# ESP32_Component.net
KiCad netlist of a schematic drawn in Altium Designer
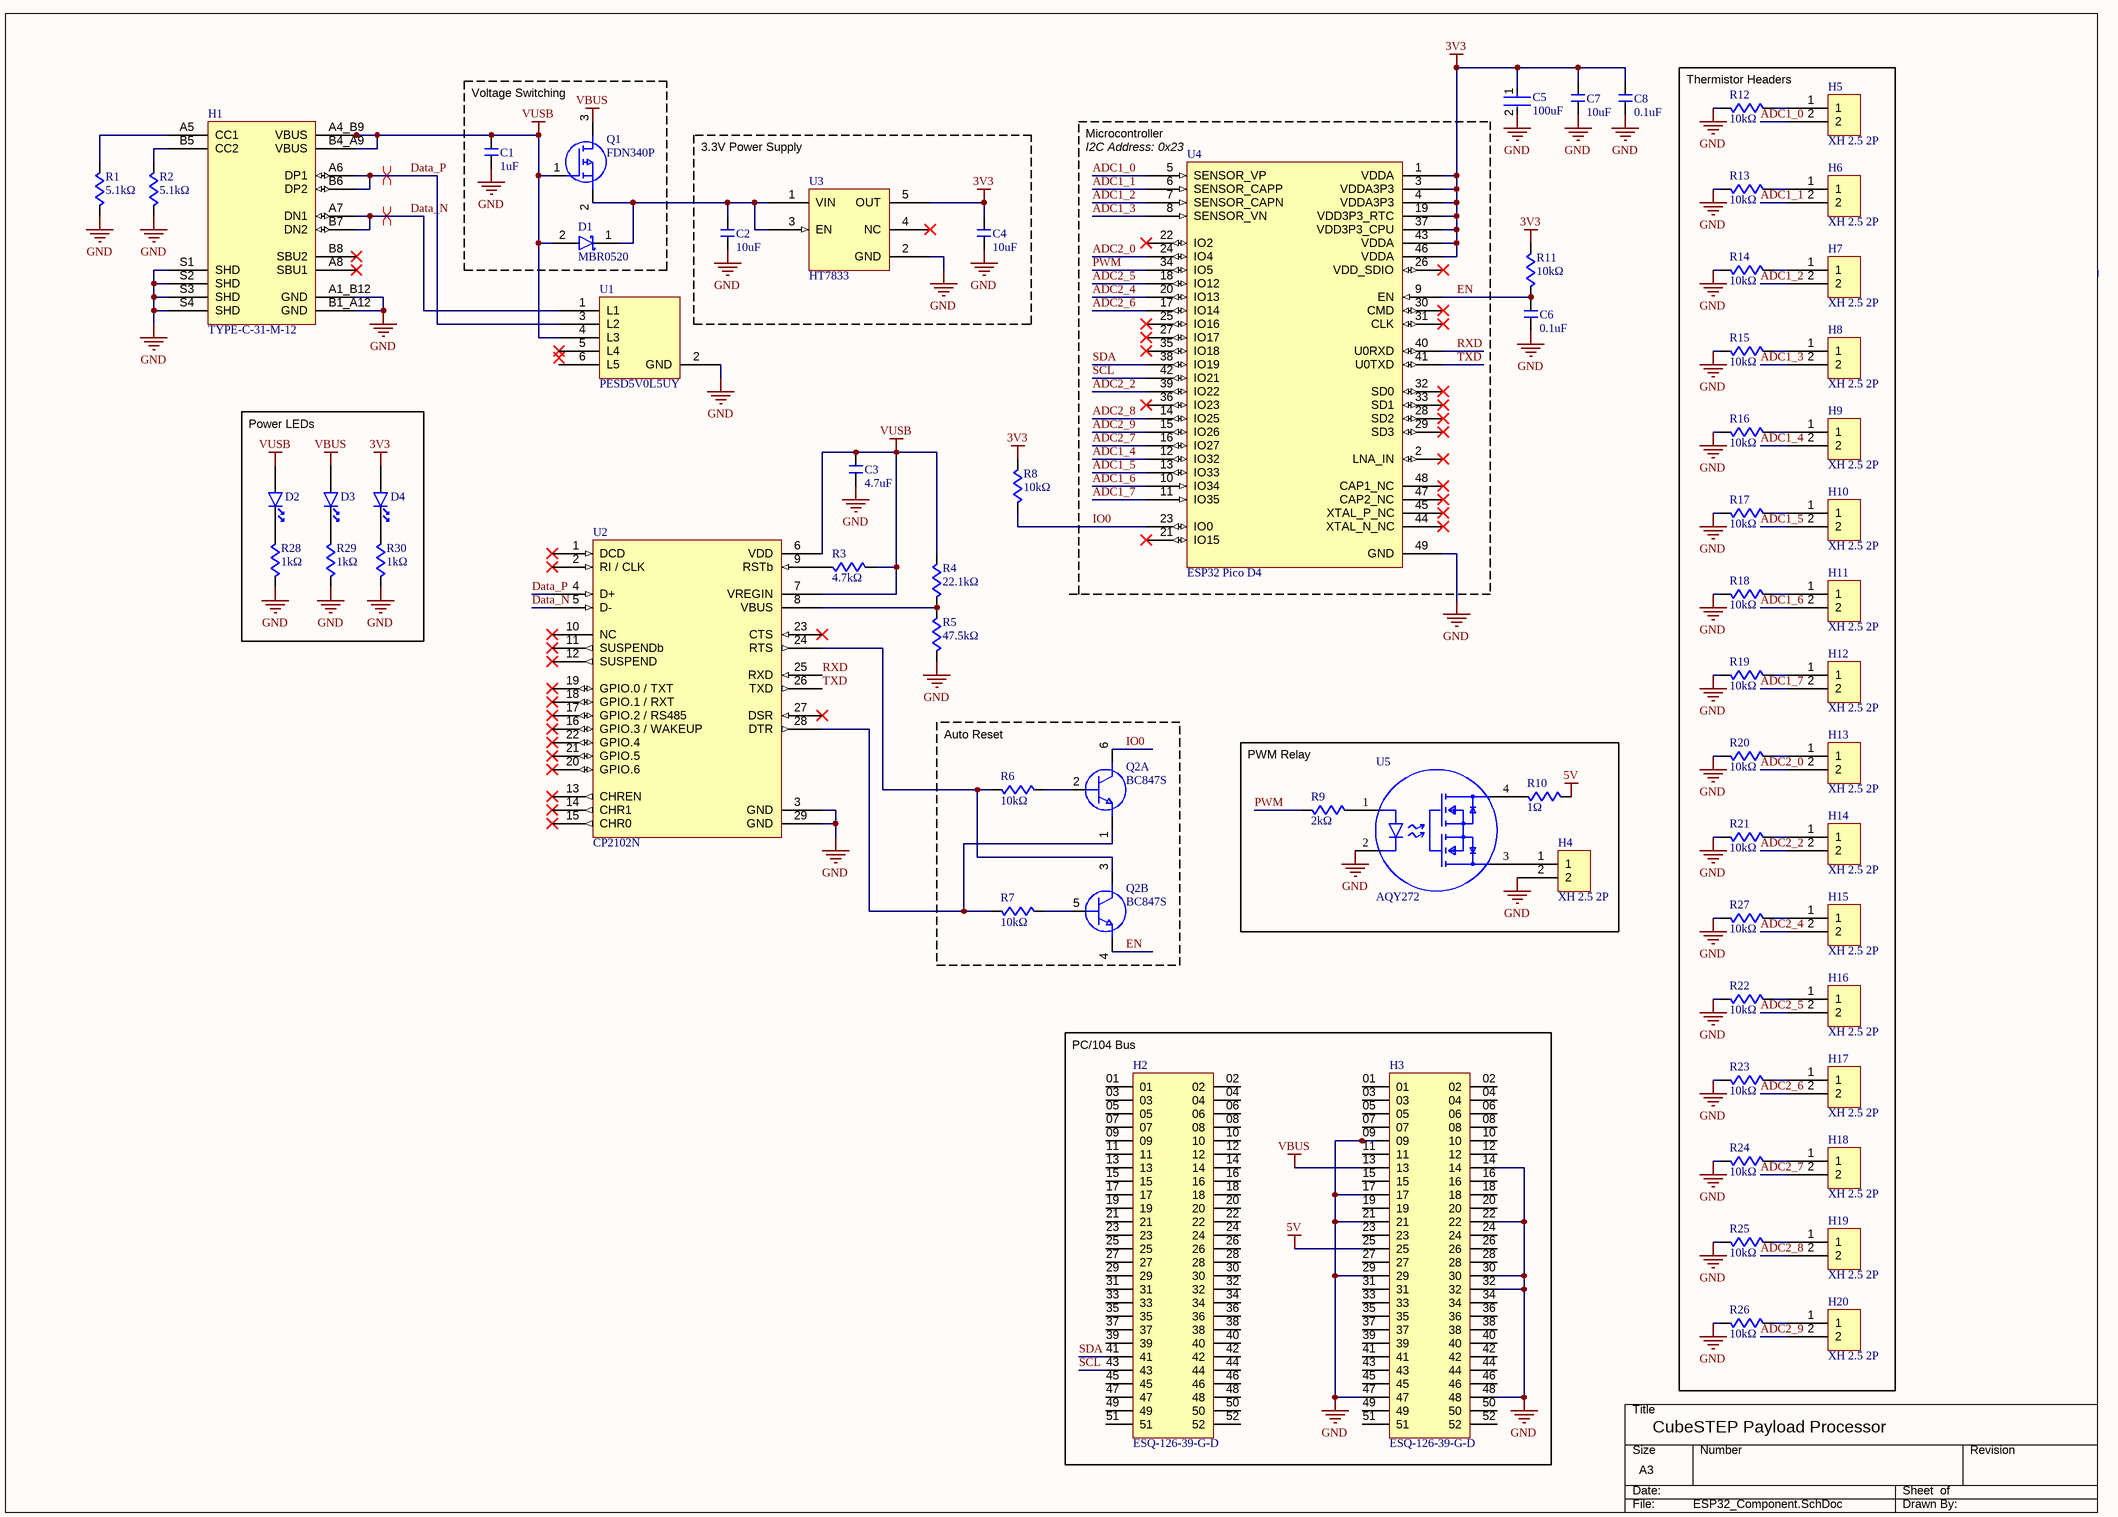
[diagram p0: ESP32_Component.SchDoc]

(export (version "E")
  (design (tool "Eeschema 10.0.6"))
  (components
    (comp (ref "C1")
      (value "1uF")
      (footprint "FP-GRM155-0_05-MFG")
      (description "±10% 16V X5R SMD 0402")
      (fields (field (name "TOLERANCE") "±10%") (field (name "MANUFACTURER") "Murata Electronics"))
      (libsource (lib "CubeSTEP Payload") (part "02cd4be3c70576c341d710602a673aa"))
    )
    (comp (ref "C2")
      (value "10uF")
      (footprint "FP-GRM21B-0_1-MFG")
      (description "±10% 16V B SMD 0805")
      (fields (field (name "PART NUMBER") "GRM21BB31C106KE15L") (field (name "TOLERANCE") "±10%"))
      (libsource (lib "CubeSTEP Payload") (part "b4654b650e69147ec39a6b967a45e02"))
    )
    (comp (ref "C3")
      (value "4.7uF")
      (footprint "TCC0402X5R104M160AT-Footprint-1")
      (description "±20% 16V X5R SMD 0402")
      (fields (field (name "TOLERANCE") "±20%") (field (name "MANUFACTURER") "--"))
      (libsource (lib "CubeSTEP Payload") (part "CM05X5R475M16AH"))
    )
    (comp (ref "C4")
      (value "10uF")
      (footprint "FP-GRM21B-0_1-MFG")
      (description "±10% 16V B SMD 0805")
      (fields (field (name "PART NUMBER") "GRM21BB31C106KE15L") (field (name "TOLERANCE") "±10%"))
      (libsource (lib "CubeSTEP Payload") (part "b4654b650e69147ec39a6b967a45e02"))
    )
    (comp (ref "C5")
      (value "100uF")
      (footprint "CAPC3216X16N")
      (description "±20% 6.3V X5R SMD 1206")
      (fields (field (name "TOLERANCE") "±20%") (field (name "PART NUMBER") "JMK316BJ107ML-T"))
      (libsource (lib "") (part "b4654b650e69147ec39a6b967a45e02_1"))
    )
    (comp (ref "C6")
      (value "0.1uF")
      (footprint "TCC0402X5R104M160AT-Footprint-1")
      (description "±20% 16V X5R SMD 0402")
      (fields (field (name "PART NUMBER") "TCC0402X5R104M160AT") (field (name "MANUFACTURER") "CCTC"))
      (libsource (lib "CubeSTEP Payload") (part "TCC0402X5R104M160AT-Symbol-1"))
    )
    (comp (ref "C7")
      (value "10uF")
      (footprint "FP-GRM21B-0_1-MFG")
      (description "±10% 16V B SMD 0805")
      (fields (field (name "PART NUMBER") "GRM21BB31C106KE15L") (field (name "TOLERANCE") "±10%"))
      (libsource (lib "CubeSTEP Payload") (part "b4654b650e69147ec39a6b967a45e02"))
    )
    (comp (ref "C8")
      (value "0.1uF")
      (footprint "TCC0402X5R104M160AT-Footprint-1")
      (description "±20% 16V X5R SMD 0402")
      (fields (field (name "PART NUMBER") "TCC0402X5R104M160AT") (field (name "MANUFACTURER") "CCTC"))
      (libsource (lib "CubeSTEP Payload") (part "TCC0402X5R104M160AT-Symbol-1"))
    )
    (comp (ref "D1")
      (value "MBR0520")
      (footprint "FP-425-04-MFG")
      (description "Rectifier Diode, Schottky, 1 Phase, 1 Element, 0.5A, 20V V(RRM), Silicon")
      (libsource (lib "CubeSTEP Payload") (part "1d6ec82d83fb6aee721767c19dac4b9"))
    )
    (comp (ref "D2")
      (value "NCD0603R2")
      (footprint "LED0603")
      (libsource (lib "CubeSTEP Payload") (part "8706943c75ba83719d021d2fdc84c58"))
    )
    (comp (ref "D3")
      (value "NCD0603R2")
      (footprint "LED0603")
      (libsource (lib "CubeSTEP Payload") (part "8706943c75ba83719d021d2fdc84c58"))
    )
    (comp (ref "D4")
      (value "NCD0603R2")
      (footprint "LED0603")
      (libsource (lib "CubeSTEP Payload") (part "8706943c75ba83719d021d2fdc84c58"))
    )
    (comp (ref "H1")
      (value "TYPE-C-31-M-12")
      (footprint "TYPE-C-31-M-12-Footprint-1")
      (description "5A 1 16P Female Type-C SMD USB Connectors ROHS")
      (libsource (lib "CubeSTEP Payload") (part "TYPE-C-31-M-12-Symbol-1"))
    )
    (comp (ref "H2")
      (value "ESQ-126-39-G-D")
      (footprint "ESQ-126-39-G-D-Footprint-1")
      (libsource (lib "CubeSTEP Payload") (part "ESQ-126-39-G-D-Symbol-1"))
    )
    (comp (ref "H3")
      (value "ESQ-126-39-G-D")
      (footprint "ESQ-126-39-G-D-Footprint-1")
      (libsource (lib "CubeSTEP Payload") (part "ESQ-126-39-G-D-Symbol-1"))
    )
    (comp (ref "H4")
      (value "XH 2.5 2P")
      (footprint "W-2501R02P-N000-Footprint-1")
      (description "1x2P XH 1 2.5mm 2 Brass Push-Pull,P=2.5mm Wire To Board / Wire To Wire Connector ROHS")
      (fields (field (name "MANUFACTURER") "Ckmtw(Shenzhen Cankemeng)"))
      (libsource (lib "CubeSTEP Payload") (part "W-2501R02P-N000"))
    )
    (comp (ref "H5")
      (value "XH 2.5 2P")
      (footprint "W-2501R02P-N000-Footprint-1")
      (description "1x2P XH 1 2.5mm 2 Brass Push-Pull,P=2.5mm Wire To Board / Wire To Wire Connector ROHS")
      (fields (field (name "MANUFACTURER") "Ckmtw(Shenzhen Cankemeng)"))
      (libsource (lib "CubeSTEP Payload") (part "W-2501R02P-N000"))
    )
    (comp (ref "H6")
      (value "XH 2.5 2P")
      (footprint "W-2501R02P-N000-Footprint-1")
      (description "1x2P XH 1 2.5mm 2 Brass Push-Pull,P=2.5mm Wire To Board / Wire To Wire Connector ROHS")
      (fields (field (name "MANUFACTURER") "Ckmtw(Shenzhen Cankemeng)"))
      (libsource (lib "CubeSTEP Payload") (part "W-2501R02P-N000"))
    )
    (comp (ref "H7")
      (value "XH 2.5 2P")
      (footprint "W-2501R02P-N000-Footprint-1")
      (description "1x2P XH 1 2.5mm 2 Brass Push-Pull,P=2.5mm Wire To Board / Wire To Wire Connector ROHS")
      (fields (field (name "MANUFACTURER") "Ckmtw(Shenzhen Cankemeng)"))
      (libsource (lib "CubeSTEP Payload") (part "W-2501R02P-N000"))
    )
    (comp (ref "H8")
      (value "XH 2.5 2P")
      (footprint "W-2501R02P-N000-Footprint-1")
      (description "1x2P XH 1 2.5mm 2 Brass Push-Pull,P=2.5mm Wire To Board / Wire To Wire Connector ROHS")
      (fields (field (name "MANUFACTURER") "Ckmtw(Shenzhen Cankemeng)"))
      (libsource (lib "CubeSTEP Payload") (part "W-2501R02P-N000"))
    )
    (comp (ref "H9")
      (value "XH 2.5 2P")
      (footprint "W-2501R02P-N000-Footprint-1")
      (description "1x2P XH 1 2.5mm 2 Brass Push-Pull,P=2.5mm Wire To Board / Wire To Wire Connector ROHS")
      (fields (field (name "MANUFACTURER") "Ckmtw(Shenzhen Cankemeng)"))
      (libsource (lib "CubeSTEP Payload") (part "W-2501R02P-N000"))
    )
    (comp (ref "H10")
      (value "XH 2.5 2P")
      (footprint "W-2501R02P-N000-Footprint-1")
      (description "1x2P XH 1 2.5mm 2 Brass Push-Pull,P=2.5mm Wire To Board / Wire To Wire Connector ROHS")
      (fields (field (name "MANUFACTURER") "Ckmtw(Shenzhen Cankemeng)"))
      (libsource (lib "CubeSTEP Payload") (part "W-2501R02P-N000"))
    )
    (comp (ref "H11")
      (value "XH 2.5 2P")
      (footprint "W-2501R02P-N000-Footprint-1")
      (description "1x2P XH 1 2.5mm 2 Brass Push-Pull,P=2.5mm Wire To Board / Wire To Wire Connector ROHS")
      (fields (field (name "MANUFACTURER") "Ckmtw(Shenzhen Cankemeng)"))
      (libsource (lib "CubeSTEP Payload") (part "W-2501R02P-N000"))
    )
    (comp (ref "H12")
      (value "XH 2.5 2P")
      (footprint "W-2501R02P-N000-Footprint-1")
      (description "1x2P XH 1 2.5mm 2 Brass Push-Pull,P=2.5mm Wire To Board / Wire To Wire Connector ROHS")
      (fields (field (name "MANUFACTURER") "Ckmtw(Shenzhen Cankemeng)"))
      (libsource (lib "CubeSTEP Payload") (part "W-2501R02P-N000"))
    )
    (comp (ref "H13")
      (value "XH 2.5 2P")
      (footprint "W-2501R02P-N000-Footprint-1")
      (description "1x2P XH 1 2.5mm 2 Brass Push-Pull,P=2.5mm Wire To Board / Wire To Wire Connector ROHS")
      (fields (field (name "MANUFACTURER") "Ckmtw(Shenzhen Cankemeng)"))
      (libsource (lib "CubeSTEP Payload") (part "W-2501R02P-N000"))
    )
    (comp (ref "H14")
      (value "XH 2.5 2P")
      (footprint "W-2501R02P-N000-Footprint-1")
      (description "1x2P XH 1 2.5mm 2 Brass Push-Pull,P=2.5mm Wire To Board / Wire To Wire Connector ROHS")
      (fields (field (name "MANUFACTURER") "Ckmtw(Shenzhen Cankemeng)"))
      (libsource (lib "CubeSTEP Payload") (part "W-2501R02P-N000"))
    )
    (comp (ref "H15")
      (value "XH 2.5 2P")
      (footprint "W-2501R02P-N000-Footprint-1")
      (description "1x2P XH 1 2.5mm 2 Brass Push-Pull,P=2.5mm Wire To Board / Wire To Wire Connector ROHS")
      (fields (field (name "MANUFACTURER") "Ckmtw(Shenzhen Cankemeng)"))
      (libsource (lib "CubeSTEP Payload") (part "W-2501R02P-N000"))
    )
    (comp (ref "H16")
      (value "XH 2.5 2P")
      (footprint "W-2501R02P-N000-Footprint-1")
      (description "1x2P XH 1 2.5mm 2 Brass Push-Pull,P=2.5mm Wire To Board / Wire To Wire Connector ROHS")
      (fields (field (name "MANUFACTURER") "Ckmtw(Shenzhen Cankemeng)"))
      (libsource (lib "CubeSTEP Payload") (part "W-2501R02P-N000"))
    )
    (comp (ref "H17")
      (value "XH 2.5 2P")
      (footprint "W-2501R02P-N000-Footprint-1")
      (description "1x2P XH 1 2.5mm 2 Brass Push-Pull,P=2.5mm Wire To Board / Wire To Wire Connector ROHS")
      (fields (field (name "MANUFACTURER") "Ckmtw(Shenzhen Cankemeng)"))
      (libsource (lib "CubeSTEP Payload") (part "W-2501R02P-N000"))
    )
    (comp (ref "H18")
      (value "XH 2.5 2P")
      (footprint "W-2501R02P-N000-Footprint-1")
      (description "1x2P XH 1 2.5mm 2 Brass Push-Pull,P=2.5mm Wire To Board / Wire To Wire Connector ROHS")
      (fields (field (name "MANUFACTURER") "Ckmtw(Shenzhen Cankemeng)"))
      (libsource (lib "CubeSTEP Payload") (part "W-2501R02P-N000"))
    )
    (comp (ref "H19")
      (value "XH 2.5 2P")
      (footprint "W-2501R02P-N000-Footprint-1")
      (description "1x2P XH 1 2.5mm 2 Brass Push-Pull,P=2.5mm Wire To Board / Wire To Wire Connector ROHS")
      (fields (field (name "MANUFACTURER") "Ckmtw(Shenzhen Cankemeng)"))
      (libsource (lib "CubeSTEP Payload") (part "W-2501R02P-N000"))
    )
    (comp (ref "H20")
      (value "XH 2.5 2P")
      (footprint "W-2501R02P-N000-Footprint-1")
      (description "1x2P XH 1 2.5mm 2 Brass Push-Pull,P=2.5mm Wire To Board / Wire To Wire Connector ROHS")
      (fields (field (name "MANUFACTURER") "Ckmtw(Shenzhen Cankemeng)"))
      (libsource (lib "CubeSTEP Payload") (part "W-2501R02P-N000"))
    )
    (comp (ref "Q1")
      (value "FDN340P")
      (footprint "FDN340P-Footprint-1")
      (description "SOT-23 MOSFETs ROHS")
      (libsource (lib "CubeSTEP Payload") (part "FDN340P-Symbol-1"))
    )
    (comp (ref "Q2")
      (value "BC847S")
      (footprint "BC847S-Footprint-1")
      (description "Small Signal Bipolar Transistor, 0.1A I(C), 45V V(BR)CEO, 2-Element, NPN, Silicon")
      (libsource (lib "CubeSTEP Payload") (part "BC847S-Symbol-1"))
    )
    (comp (ref "R1")
      (value "5.1kΩ")
      (footprint "RESC1005X04N")
      (description "±0.5% 62.5mW 50V SMD 0402")
      (fields (field (name "TOLERANCE") "±0.5%") (field (name "MANUFACTURER") "UNI-ROYAL(Uniroyal Elec)"))
      (libsource (lib "CubeSTEP Payload") (part "RC-02W1002FT"))
    )
    (comp (ref "R2")
      (value "5.1kΩ")
      (footprint "RESC1005X04N")
      (description "±0.5% 62.5mW 50V SMD 0402")
      (fields (field (name "TOLERANCE") "±0.5%") (field (name "MANUFACTURER") "UNI-ROYAL(Uniroyal Elec)"))
      (libsource (lib "CubeSTEP Payload") (part "RC-02W1002FT"))
    )
    (comp (ref "R3")
      (value "4.7kΩ")
      (footprint "RESC1005X04N")
      (description "±1% 62.5mW 50V SMD 0402")
      (fields (field (name "MANUFACTURER") "YAGEO") (field (name "TOLERANCE") "±1%"))
      (libsource (lib "CubeSTEP Payload") (part "RC-02W1002FT"))
    )
    (comp (ref "R4")
      (value "22.1kΩ")
      (footprint "RESC1005X04N")
      (description "±1% 62.5mW50V SMD 0402")
      (fields (field (name "PART NUMBER") "RC0402FR-0722K1L") (field (name "TOLERANCE") "±1%"))
      (libsource (lib "CubeSTEP Payload") (part "RC-02W1002FT"))
    )
    (comp (ref "R5")
      (value "47.5kΩ")
      (footprint "RESC1005X04N")
      (description "±1% 62.5mW 50V SMD 0402")
      (fields (field (name "TOLERANCE") "±1%") (field (name "POWER") "62.5mW"))
      (libsource (lib "CubeSTEP Payload") (part "RC-02W1002FT"))
    )
    (comp (ref "R6")
      (value "10kΩ")
      (footprint "RESC1005X04N")
      (description "±1% 62.5mW 50V SMD 0402")
      (fields (field (name "PART NUMBER") "RC-02W1002FT") (field (name "POWER") "62.5mW"))
      (libsource (lib "CubeSTEP Payload") (part "RC-02W1002FT"))
    )
    (comp (ref "R7")
      (value "10kΩ")
      (footprint "RESC1005X04N")
      (description "±1% 62.5mW 50V SMD 0402")
      (fields (field (name "PART NUMBER") "RC-02W1002FT") (field (name "POWER") "62.5mW"))
      (libsource (lib "CubeSTEP Payload") (part "RC-02W1002FT"))
    )
    (comp (ref "R8")
      (value "10kΩ")
      (footprint "RESC1005X04N")
      (description "±1% 62.5mW 50V SMD 0402")
      (fields (field (name "PART NUMBER") "RC-02W1002FT") (field (name "POWER") "62.5mW"))
      (libsource (lib "CubeSTEP Payload") (part "RC-02W1002FT"))
    )
    (comp (ref "R9")
      (value "2kΩ")
      (footprint "RESC1005X04N")
      (description "±1% 62.5mW 50V SMD 0402")
      (fields (field (name "PART NUMBER") "CR0402FF2001G") (field (name "MANUFACTURER") "LIZ Elec"))
      (libsource (lib "CubeSTEP Payload") (part "RC-02W1002FT"))
    )
    (comp (ref "R10")
      (value "1Ω")
      (footprint "RESC5025X04N")
      (description "±5% 0.75W 200V SMD 2010")
      (fields (field (name "PART NUMBER") "RTT201R00FTE") (field (name "TOLERANCE") "±5%"))
      (libsource (lib "CubeSTEP Payload") (part "RC-02W1002FT"))
    )
    (comp (ref "R11")
      (value "10kΩ")
      (footprint "RESC1005X04N")
      (description "±1% 62.5mW 50V SMD 0402")
      (fields (field (name "PART NUMBER") "RC-02W1002FT") (field (name "POWER") "62.5mW"))
      (libsource (lib "CubeSTEP Payload") (part "RC-02W1002FT"))
    )
    (comp (ref "R12")
      (value "10kΩ")
      (footprint "RESC1005X04N")
      (description "±1% 62.5mW 50V SMD 0402")
      (fields (field (name "PART NUMBER") "RC-02W1002FT") (field (name "POWER") "62.5mW"))
      (libsource (lib "CubeSTEP Payload") (part "RC-02W1002FT"))
    )
    (comp (ref "R13")
      (value "10kΩ")
      (footprint "RESC1005X04N")
      (description "±1% 62.5mW 50V SMD 0402")
      (fields (field (name "PART NUMBER") "RC-02W1002FT") (field (name "POWER") "62.5mW"))
      (libsource (lib "CubeSTEP Payload") (part "RC-02W1002FT"))
    )
    (comp (ref "R14")
      (value "10kΩ")
      (footprint "RESC1005X04N")
      (description "±1% 62.5mW 50V SMD 0402")
      (fields (field (name "PART NUMBER") "RC-02W1002FT") (field (name "POWER") "62.5mW"))
      (libsource (lib "CubeSTEP Payload") (part "RC-02W1002FT"))
    )
    (comp (ref "R15")
      (value "10kΩ")
      (footprint "RESC1005X04N")
      (description "±1% 62.5mW 50V SMD 0402")
      (fields (field (name "PART NUMBER") "RC-02W1002FT") (field (name "POWER") "62.5mW"))
      (libsource (lib "CubeSTEP Payload") (part "RC-02W1002FT"))
    )
    (comp (ref "R16")
      (value "10kΩ")
      (footprint "RESC1005X04N")
      (description "±1% 62.5mW 50V SMD 0402")
      (fields (field (name "PART NUMBER") "RC-02W1002FT") (field (name "POWER") "62.5mW"))
      (libsource (lib "CubeSTEP Payload") (part "RC-02W1002FT"))
    )
    (comp (ref "R17")
      (value "10kΩ")
      (footprint "RESC1005X04N")
      (description "±1% 62.5mW 50V SMD 0402")
      (fields (field (name "PART NUMBER") "RC-02W1002FT") (field (name "POWER") "62.5mW"))
      (libsource (lib "CubeSTEP Payload") (part "RC-02W1002FT"))
    )
    (comp (ref "R18")
      (value "10kΩ")
      (footprint "RESC1005X04N")
      (description "±1% 62.5mW 50V SMD 0402")
      (fields (field (name "PART NUMBER") "RC-02W1002FT") (field (name "POWER") "62.5mW"))
      (libsource (lib "CubeSTEP Payload") (part "RC-02W1002FT"))
    )
    (comp (ref "R19")
      (value "10kΩ")
      (footprint "RESC1005X04N")
      (description "±1% 62.5mW 50V SMD 0402")
      (fields (field (name "PART NUMBER") "RC-02W1002FT") (field (name "POWER") "62.5mW"))
      (libsource (lib "CubeSTEP Payload") (part "RC-02W1002FT"))
    )
    (comp (ref "R20")
      (value "10kΩ")
      (footprint "RESC1005X04N")
      (description "±1% 62.5mW 50V SMD 0402")
      (fields (field (name "PART NUMBER") "RC-02W1002FT") (field (name "POWER") "62.5mW"))
      (libsource (lib "CubeSTEP Payload") (part "RC-02W1002FT"))
    )
    (comp (ref "R21")
      (value "10kΩ")
      (footprint "RESC1005X04N")
      (description "±1% 62.5mW 50V SMD 0402")
      (fields (field (name "PART NUMBER") "RC-02W1002FT") (field (name "POWER") "62.5mW"))
      (libsource (lib "CubeSTEP Payload") (part "RC-02W1002FT"))
    )
    (comp (ref "R22")
      (value "10kΩ")
      (footprint "RESC1005X04N")
      (description "±1% 62.5mW 50V SMD 0402")
      (fields (field (name "PART NUMBER") "RC-02W1002FT") (field (name "POWER") "62.5mW"))
      (libsource (lib "CubeSTEP Payload") (part "RC-02W1002FT"))
    )
    (comp (ref "R23")
      (value "10kΩ")
      (footprint "RESC1005X04N")
      (description "±1% 62.5mW 50V SMD 0402")
      (fields (field (name "PART NUMBER") "RC-02W1002FT") (field (name "POWER") "62.5mW"))
      (libsource (lib "CubeSTEP Payload") (part "RC-02W1002FT"))
    )
    (comp (ref "R24")
      (value "10kΩ")
      (footprint "RESC1005X04N")
      (description "±1% 62.5mW 50V SMD 0402")
      (fields (field (name "PART NUMBER") "RC-02W1002FT") (field (name "POWER") "62.5mW"))
      (libsource (lib "CubeSTEP Payload") (part "RC-02W1002FT"))
    )
    (comp (ref "R25")
      (value "10kΩ")
      (footprint "RESC1005X04N")
      (description "±1% 62.5mW 50V SMD 0402")
      (fields (field (name "PART NUMBER") "RC-02W1002FT") (field (name "POWER") "62.5mW"))
      (libsource (lib "CubeSTEP Payload") (part "RC-02W1002FT"))
    )
    (comp (ref "R26")
      (value "10kΩ")
      (footprint "RESC1005X04N")
      (description "±1% 62.5mW 50V SMD 0402")
      (fields (field (name "PART NUMBER") "RC-02W1002FT") (field (name "POWER") "62.5mW"))
      (libsource (lib "CubeSTEP Payload") (part "RC-02W1002FT"))
    )
    (comp (ref "R27")
      (value "10kΩ")
      (footprint "RESC1005X04N")
      (description "±1% 62.5mW 50V SMD 0402")
      (fields (field (name "PART NUMBER") "RC-02W1002FT") (field (name "POWER") "62.5mW"))
      (libsource (lib "CubeSTEP Payload") (part "RC-02W1002FT"))
    )
    (comp (ref "R28")
      (value "1kΩ")
      (footprint "RESC1005X04N")
      (description "±1% 62.5mW 50V SMD 0402")
      (fields (field (name "POWER") "62.5mW") (field (name "MANUFACTURER") "YAGEO"))
      (libsource (lib "CubeSTEP Payload") (part "RC-02W1002FT"))
    )
    (comp (ref "R29")
      (value "1kΩ")
      (footprint "RESC1005X04N")
      (description "±1% 62.5mW 50V SMD 0402")
      (fields (field (name "POWER") "62.5mW") (field (name "MANUFACTURER") "YAGEO"))
      (libsource (lib "CubeSTEP Payload") (part "RC-02W1002FT"))
    )
    (comp (ref "R30")
      (value "1kΩ")
      (footprint "RESC1005X04N")
      (description "±1% 62.5mW 50V SMD 0402")
      (fields (field (name "POWER") "62.5mW") (field (name "MANUFACTURER") "YAGEO"))
      (libsource (lib "CubeSTEP Payload") (part "RC-02W1002FT"))
    )
    (comp (ref "U1")
      (value "PESD5V0L5UY")
      (footprint "PESD5V0L5UY-Footprint-1")
      (description "Trans Voltage Suppressor Diode, 25W, 5V V(RWM), Unidirectional, 5 Element, Silicon")
      (fields (field (name "MANUFACTURER") "UMW(Youtai Semiconductor Co., Ltd.)"))
      (libsource (lib "CubeSTEP Payload") (part "PESD5V0L5UY"))
    )
    (comp (ref "U2")
      (value "CP2102N")
      (footprint "CP2102N-A02-GQFN28R-Footprint-1")
      (description "USB-to-UART bridge controller")
      (fields (field (name "PART NUMBER") "CP2102N-A02-GQFN28R") (field (name "MANUFACTURER") "SILICON LABS"))
      (libsource (lib "CubeSTEP Payload") (part "CP2102N-A02-GQFN28R"))
    )
    (comp (ref "U3")
      (value "HT7833")
      (footprint "HT7833-Footprint-1")
      (description "SOT-23-5 Linear Voltage Regulators (LDO) ROHS")
      (fields (field (name "MANUFACTURER") "TECH PUBLIC"))
      (libsource (lib "CubeSTEP Payload") (part "HT7833"))
    )
    (comp (ref "U4")
      (value "ESP32 Pico D4")
      (footprint "ESP32-PICO-D4-Footprint-1")
      (description "System-on-Chip integrating an ESP32 chip together with a 4 MB SPI flash")
      (fields (field (name "MANUFACTURER") "Espressif Systems") (field (name "PART NUMBER") "ESP32-PICO-D4"))
      (libsource (lib "CubeSTEP Payload") (part "ESP32-PICO-D4-Symbol-1"))
    )
    (comp (ref "U5")
      (value "AQY272")
      (footprint "FP-AQY272-MFG")
      (description "Solid State Relays 1.25V 60V 0.11Ω 2A AC,DC DIP-4 - MOS Output (PhotoMOS) ROHS 1 Form A(SPST-NO)")
      (libsource (lib "CubeSTEP Payload") (part "b48b7fcafc852751f620c383186d6b0"))
    )
  )
  (nets
    (net (code "1") (name "/ADC1_0") (class "Default")
      (node (ref "H5") (pin "2") (pinfunction "2_2") (pintype "passive"))
      (node (ref "U4") (pin "5") (pinfunction "SENSOR_VP_5") (pintype "input"))
    )
    (net (code "2") (name "/ADC1_1") (class "Default")
      (node (ref "H6") (pin "2") (pinfunction "2_2") (pintype "passive"))
      (node (ref "U4") (pin "6") (pinfunction "SENSOR_CAPP_6") (pintype "input"))
    )
    (net (code "3") (name "/ADC1_2") (class "Default")
      (node (ref "H7") (pin "2") (pinfunction "2_2") (pintype "passive"))
      (node (ref "U4") (pin "7") (pinfunction "SENSOR_CAPN_7") (pintype "input"))
    )
    (net (code "4") (name "/ADC1_3") (class "Default")
      (node (ref "H8") (pin "2") (pinfunction "2_2") (pintype "passive"))
      (node (ref "U4") (pin "8") (pinfunction "SENSOR_VN_8") (pintype "input"))
    )
    (net (code "5") (name "/ADC1_4") (class "Default")
      (node (ref "H9") (pin "2") (pinfunction "2_2") (pintype "passive"))
      (node (ref "U4") (pin "12") (pinfunction "IO32_12") (pintype "bidirectional"))
    )
    (net (code "6") (name "/ADC1_5") (class "Default")
      (node (ref "H10") (pin "2") (pinfunction "2_2") (pintype "passive"))
      (node (ref "U4") (pin "13") (pinfunction "IO33_13") (pintype "bidirectional"))
    )
    (net (code "7") (name "/ADC1_6") (class "Default")
      (node (ref "H11") (pin "2") (pinfunction "2_2") (pintype "passive"))
      (node (ref "U4") (pin "10") (pinfunction "IO34_10") (pintype "input"))
    )
    (net (code "8") (name "/ADC1_7") (class "Default")
      (node (ref "H12") (pin "2") (pinfunction "2_2") (pintype "passive"))
      (node (ref "U4") (pin "11") (pinfunction "IO35_11") (pintype "input"))
    )
    (net (code "9") (name "/ADC2_0") (class "Default")
      (node (ref "H13") (pin "2") (pinfunction "2_2") (pintype "passive"))
      (node (ref "U4") (pin "24") (pinfunction "IO4_24") (pintype "bidirectional"))
    )
    (net (code "10") (name "/ADC2_2") (class "Default")
      (node (ref "H14") (pin "2") (pinfunction "2_2") (pintype "passive"))
      (node (ref "U4") (pin "39") (pinfunction "IO22_39") (pintype "bidirectional"))
    )
    (net (code "11") (name "/ADC2_4") (class "Default")
      (node (ref "H15") (pin "2") (pinfunction "2_2") (pintype "passive"))
      (node (ref "U4") (pin "20") (pinfunction "IO13_20") (pintype "bidirectional"))
    )
    (net (code "12") (name "/ADC2_5") (class "Default")
      (node (ref "H16") (pin "2") (pinfunction "2_2") (pintype "passive"))
      (node (ref "U4") (pin "18") (pinfunction "IO12_18") (pintype "bidirectional"))
    )
    (net (code "13") (name "/ADC2_6") (class "Default")
      (node (ref "H17") (pin "2") (pinfunction "2_2") (pintype "passive"))
      (node (ref "U4") (pin "17") (pinfunction "IO14_17") (pintype "bidirectional"))
    )
    (net (code "14") (name "/ADC2_7") (class "Default")
      (node (ref "H18") (pin "2") (pinfunction "2_2") (pintype "passive"))
      (node (ref "U4") (pin "16") (pinfunction "IO27_16") (pintype "bidirectional"))
    )
    (net (code "15") (name "/ADC2_8") (class "Default")
      (node (ref "H19") (pin "2") (pinfunction "2_2") (pintype "passive"))
      (node (ref "U4") (pin "14") (pinfunction "IO25_14") (pintype "bidirectional"))
    )
    (net (code "16") (name "/ADC2_9") (class "Default")
      (node (ref "H20") (pin "2") (pinfunction "2_2") (pintype "passive"))
      (node (ref "U4") (pin "15") (pinfunction "IO26_15") (pintype "bidirectional"))
    )
    (net (code "17") (name "/Data_N") (class "Default")
      (node (ref "H1") (pin "A7") (pinfunction "DN1_A7") (pintype "bidirectional"))
      (node (ref "H1") (pin "B7") (pinfunction "DN2_B7") (pintype "bidirectional"))
      (node (ref "U1") (pin "1") (pinfunction "L1_1") (pintype "passive"))
      (node (ref "U2") (pin "5") (pinfunction "D-_5") (pintype "input"))
    )
    (net (code "18") (name "/Data_P") (class "Default")
      (node (ref "H1") (pin "A6") (pinfunction "DP1_A6") (pintype "bidirectional"))
      (node (ref "H1") (pin "B6") (pinfunction "DP2_B6") (pintype "bidirectional"))
      (node (ref "U1") (pin "3") (pinfunction "L2_3") (pintype "passive"))
      (node (ref "U2") (pin "4") (pinfunction "D+_4") (pintype "input"))
    )
    (net (code "19") (name "/EN") (class "Default")
      (node (ref "C6") (pin "2") (pinfunction "2_2") (pintype "passive"))
      (node (ref "Q2") (pin "4") (pinfunction "S_4") (pintype "passive"))
      (node (ref "R11") (pin "1") (pinfunction "1_1") (pintype "passive"))
      (node (ref "U4") (pin "9") (pinfunction "EN_9") (pintype "input"))
    )
    (net (code "20") (name "/IO0") (class "Default")
      (node (ref "Q2") (pin "6") (pinfunction "D_6") (pintype "passive"))
      (node (ref "R8") (pin "1") (pinfunction "1_1") (pintype "passive"))
      (node (ref "U4") (pin "23") (pinfunction "IO0_23") (pintype "bidirectional"))
    )
    (net (code "21") (name "/PWM") (class "Default")
      (node (ref "R9") (pin "1") (pinfunction "1_1") (pintype "passive"))
      (node (ref "U4") (pin "34") (pinfunction "IO5_34") (pintype "bidirectional"))
    )
    (net (code "22") (name "/RXD") (class "Default")
      (node (ref "U2") (pin "25") (pinfunction "RXD_25") (pintype "input"))
      (node (ref "U4") (pin "40") (pinfunction "U0RXD_40") (pintype "bidirectional"))
    )
    (net (code "23") (name "/SCL") (class "Default")
      (node (ref "H2") (pin "43") (pinfunction "43_43") (pintype "passive"))
      (node (ref "U4") (pin "42") (pinfunction "IO21_42") (pintype "bidirectional"))
    )
    (net (code "24") (name "/SDA") (class "Default")
      (node (ref "H2") (pin "41") (pinfunction "41_41") (pintype "passive"))
      (node (ref "U4") (pin "38") (pinfunction "IO19_38") (pintype "bidirectional"))
    )
    (net (code "25") (name "/TXD") (class "Default")
      (node (ref "U2") (pin "26") (pinfunction "TXD_26") (pintype "output"))
      (node (ref "U4") (pin "41") (pinfunction "U0TXD_41") (pintype "bidirectional"))
    )
    (net (code "26") (name "3V3") (class "Default")
      (node (ref "C4") (pin "2") (pinfunction "2_2") (pintype "passive"))
      (node (ref "C5") (pin "1") (pinfunction "1_1") (pintype "passive"))
      (node (ref "C7") (pin "2") (pinfunction "2_2") (pintype "passive"))
      (node (ref "C8") (pin "2") (pinfunction "2_2") (pintype "passive"))
      (node (ref "D4") (pin "2") (pinfunction "A_2") (pintype "passive"))
      (node (ref "R11") (pin "2") (pinfunction "2_2") (pintype "passive"))
      (node (ref "R8") (pin "2") (pinfunction "2_2") (pintype "passive"))
      (node (ref "U3") (pin "5") (pinfunction "OUT_5") (pintype "power_in"))
      (node (ref "U4") (pin "1") (pinfunction "VDDA_1") (pintype "power_in"))
      (node (ref "U4") (pin "19") (pinfunction "VDD3P3_RTC_19") (pintype "power_in"))
      (node (ref "U4") (pin "3") (pinfunction "VDDA3P3_3") (pintype "power_in"))
      (node (ref "U4") (pin "37") (pinfunction "VDD3P3_CPU_37") (pintype "power_in"))
      (node (ref "U4") (pin "4") (pinfunction "VDDA3P3_4") (pintype "power_in"))
      (node (ref "U4") (pin "43") (pinfunction "VDDA_43") (pintype "power_in"))
      (node (ref "U4") (pin "46") (pinfunction "VDDA_46") (pintype "power_in"))
    )
    (net (code "27") (name "5V") (class "Default")
      (node (ref "H3") (pin "25") (pinfunction "25_25") (pintype "passive"))
      (node (ref "R10") (pin "2") (pinfunction "2_2") (pintype "passive"))
    )
    (net (code "28") (name "GND") (class "Default")
      (node (ref "C1") (pin "2") (pinfunction "2_2") (pintype "passive"))
      (node (ref "C2") (pin "1") (pinfunction "1_1") (pintype "passive"))
      (node (ref "C3") (pin "2") (pinfunction "2_2") (pintype "passive"))
      (node (ref "C4") (pin "1") (pinfunction "1_1") (pintype "passive"))
      (node (ref "C5") (pin "2") (pinfunction "2_2") (pintype "passive"))
      (node (ref "C6") (pin "1") (pinfunction "1_1") (pintype "passive"))
      (node (ref "C7") (pin "1") (pinfunction "1_1") (pintype "passive"))
      (node (ref "C8") (pin "1") (pinfunction "1_1") (pintype "passive"))
      (node (ref "H1") (pin "A1_B12") (pinfunction "GND_A1_B12") (pintype "power_in"))
      (node (ref "H1") (pin "B1_A12") (pinfunction "GND_B1_A12") (pintype "power_in"))
      (node (ref "H1") (pin "S1") (pinfunction "SHD_S1") (pintype "power_in"))
      (node (ref "H1") (pin "S2") (pinfunction "SHD_S2") (pintype "power_in"))
      (node (ref "H1") (pin "S3") (pinfunction "SHD_S3") (pintype "power_in"))
      (node (ref "H1") (pin "S4") (pinfunction "SHD_S4") (pintype "power_in"))
      (node (ref "H3") (pin "09") (pinfunction "09_09") (pintype "passive"))
      (node (ref "H3") (pin "14") (pinfunction "14_14") (pintype "passive"))
      (node (ref "H3") (pin "17") (pinfunction "17_17") (pintype "passive"))
      (node (ref "H3") (pin "21") (pinfunction "21_21") (pintype "passive"))
      (node (ref "H3") (pin "22") (pinfunction "22_22") (pintype "passive"))
      (node (ref "H3") (pin "29") (pinfunction "29_29") (pintype "passive"))
      (node (ref "H3") (pin "30") (pinfunction "30_30") (pintype "passive"))
      (node (ref "H3") (pin "32") (pinfunction "32_32") (pintype "passive"))
      (node (ref "H3") (pin "47") (pinfunction "47_47") (pintype "passive"))
      (node (ref "H3") (pin "48") (pinfunction "48_48") (pintype "passive"))
      (node (ref "H4") (pin "2") (pinfunction "2_2") (pintype "passive"))
      (node (ref "R1") (pin "1") (pinfunction "1_1") (pintype "passive"))
      (node (ref "R12") (pin "2") (pinfunction "2_2") (pintype "passive"))
      (node (ref "R13") (pin "1") (pinfunction "1_1") (pintype "passive"))
      (node (ref "R14") (pin "1") (pinfunction "1_1") (pintype "passive"))
      (node (ref "R15") (pin "1") (pinfunction "1_1") (pintype "passive"))
      (node (ref "R16") (pin "1") (pinfunction "1_1") (pintype "passive"))
      (node (ref "R17") (pin "1") (pinfunction "1_1") (pintype "passive"))
      (node (ref "R18") (pin "1") (pinfunction "1_1") (pintype "passive"))
      (node (ref "R19") (pin "1") (pinfunction "1_1") (pintype "passive"))
      (node (ref "R2") (pin "1") (pinfunction "1_1") (pintype "passive"))
      (node (ref "R20") (pin "1") (pinfunction "1_1") (pintype "passive"))
      (node (ref "R21") (pin "1") (pinfunction "1_1") (pintype "passive"))
      (node (ref "R22") (pin "1") (pinfunction "1_1") (pintype "passive"))
      (node (ref "R23") (pin "1") (pinfunction "1_1") (pintype "passive"))
      (node (ref "R24") (pin "1") (pinfunction "1_1") (pintype "passive"))
      (node (ref "R25") (pin "1") (pinfunction "1_1") (pintype "passive"))
      (node (ref "R26") (pin "1") (pinfunction "1_1") (pintype "passive"))
      (node (ref "R27") (pin "1") (pinfunction "1_1") (pintype "passive"))
      (node (ref "R28") (pin "1") (pinfunction "1_1") (pintype "passive"))
      (node (ref "R29") (pin "1") (pinfunction "1_1") (pintype "passive"))
      (node (ref "R30") (pin "1") (pinfunction "1_1") (pintype "passive"))
      (node (ref "R5") (pin "1") (pinfunction "1_1") (pintype "passive"))
      (node (ref "U1") (pin "2") (pinfunction "GND_2") (pintype "power_in"))
      (node (ref "U2") (pin "29") (pinfunction "GND_29") (pintype "power_in"))
      (node (ref "U2") (pin "3") (pinfunction "GND_3") (pintype "power_in"))
      (node (ref "U3") (pin "2") (pinfunction "GND_2") (pintype "power_in"))
      (node (ref "U4") (pin "49") (pinfunction "GND_49") (pintype "power_in"))
      (node (ref "U5") (pin "2") (pinfunction "C_2") (pintype "passive"))
    )
    (net (code "29") (name "Net-(D1-C)") (class "Default")
      (node (ref "C2") (pin "2") (pinfunction "2_2") (pintype "passive"))
      (node (ref "D1") (pin "1") (pinfunction "C_1") (pintype "passive"))
      (node (ref "Q1") (pin "2") (pinfunction "S_2") (pintype "passive"))
      (node (ref "U3") (pin "1") (pinfunction "VIN_1") (pintype "power_in"))
      (node (ref "U3") (pin "3") (pinfunction "EN_3") (pintype "input"))
    )
    (net (code "30") (name "Net-(D2-C)") (class "Default")
      (node (ref "D2") (pin "1") (pinfunction "C_1") (pintype "passive"))
      (node (ref "R28") (pin "2") (pinfunction "2_2") (pintype "passive"))
    )
    (net (code "31") (name "Net-(D3-C)") (class "Default")
      (node (ref "D3") (pin "1") (pinfunction "C_1") (pintype "passive"))
      (node (ref "R29") (pin "2") (pinfunction "2_2") (pintype "passive"))
    )
    (net (code "32") (name "Net-(D4-C)") (class "Default")
      (node (ref "D4") (pin "1") (pinfunction "C_1") (pintype "passive"))
      (node (ref "R30") (pin "2") (pinfunction "2_2") (pintype "passive"))
    )
    (net (code "33") (name "Net-(H1-CC1)") (class "Default")
      (node (ref "H1") (pin "A5") (pinfunction "CC1_A5") (pintype "passive"))
      (node (ref "R1") (pin "2") (pinfunction "2_2") (pintype "passive"))
    )
    (net (code "34") (name "Net-(H1-CC2)") (class "Default")
      (node (ref "H1") (pin "B5") (pinfunction "CC2_B5") (pintype "passive"))
      (node (ref "R2") (pin "2") (pinfunction "2_2") (pintype "passive"))
    )
    (net (code "35") (name "Net-(H5-Pad1)") (class "Default")
      (node (ref "H5") (pin "1") (pinfunction "1_1") (pintype "passive"))
      (node (ref "R12") (pin "1") (pinfunction "1_1") (pintype "passive"))
    )
    (net (code "36") (name "Net-(H6-Pad1)") (class "Default")
      (node (ref "H6") (pin "1") (pinfunction "1_1") (pintype "passive"))
      (node (ref "R13") (pin "2") (pinfunction "2_2") (pintype "passive"))
    )
    (net (code "37") (name "Net-(H7-Pad1)") (class "Default")
      (node (ref "H7") (pin "1") (pinfunction "1_1") (pintype "passive"))
      (node (ref "R14") (pin "2") (pinfunction "2_2") (pintype "passive"))
    )
    (net (code "38") (name "Net-(H8-Pad1)") (class "Default")
      (node (ref "H8") (pin "1") (pinfunction "1_1") (pintype "passive"))
      (node (ref "R15") (pin "2") (pinfunction "2_2") (pintype "passive"))
    )
    (net (code "39") (name "Net-(H9-Pad1)") (class "Default")
      (node (ref "H9") (pin "1") (pinfunction "1_1") (pintype "passive"))
      (node (ref "R16") (pin "2") (pinfunction "2_2") (pintype "passive"))
    )
    (net (code "40") (name "Net-(H10-Pad1)") (class "Default")
      (node (ref "H10") (pin "1") (pinfunction "1_1") (pintype "passive"))
      (node (ref "R17") (pin "2") (pinfunction "2_2") (pintype "passive"))
    )
    (net (code "41") (name "Net-(H11-Pad1)") (class "Default")
      (node (ref "H11") (pin "1") (pinfunction "1_1") (pintype "passive"))
      (node (ref "R18") (pin "2") (pinfunction "2_2") (pintype "passive"))
    )
    (net (code "42") (name "Net-(H12-Pad1)") (class "Default")
      (node (ref "H12") (pin "1") (pinfunction "1_1") (pintype "passive"))
      (node (ref "R19") (pin "2") (pinfunction "2_2") (pintype "passive"))
    )
    (net (code "43") (name "Net-(H13-Pad1)") (class "Default")
      (node (ref "H13") (pin "1") (pinfunction "1_1") (pintype "passive"))
      (node (ref "R20") (pin "2") (pinfunction "2_2") (pintype "passive"))
    )
    (net (code "44") (name "Net-(H14-Pad1)") (class "Default")
      (node (ref "H14") (pin "1") (pinfunction "1_1") (pintype "passive"))
      (node (ref "R21") (pin "2") (pinfunction "2_2") (pintype "passive"))
    )
    (net (code "45") (name "Net-(H15-Pad1)") (class "Default")
      (node (ref "H15") (pin "1") (pinfunction "1_1") (pintype "passive"))
      (node (ref "R27") (pin "2") (pinfunction "2_2") (pintype "passive"))
    )
    (net (code "46") (name "Net-(H16-Pad1)") (class "Default")
      (node (ref "H16") (pin "1") (pinfunction "1_1") (pintype "passive"))
      (node (ref "R22") (pin "2") (pinfunction "2_2") (pintype "passive"))
    )
    (net (code "47") (name "Net-(H17-Pad1)") (class "Default")
      (node (ref "H17") (pin "1") (pinfunction "1_1") (pintype "passive"))
      (node (ref "R23") (pin "2") (pinfunction "2_2") (pintype "passive"))
    )
    (net (code "48") (name "Net-(H18-Pad1)") (class "Default")
      (node (ref "H18") (pin "1") (pinfunction "1_1") (pintype "passive"))
      (node (ref "R24") (pin "2") (pinfunction "2_2") (pintype "passive"))
    )
    (net (code "49") (name "Net-(H19-Pad1)") (class "Default")
      (node (ref "H19") (pin "1") (pinfunction "1_1") (pintype "passive"))
      (node (ref "R25") (pin "2") (pinfunction "2_2") (pintype "passive"))
    )
    (net (code "50") (name "Net-(H20-Pad1)") (class "Default")
      (node (ref "H20") (pin "1") (pinfunction "1_1") (pintype "passive"))
      (node (ref "R26") (pin "2") (pinfunction "2_2") (pintype "passive"))
    )
    (net (code "51") (name "Net-(Q2A-G)") (class "Default")
      (node (ref "Q2") (pin "2") (pinfunction "G_2") (pintype "passive"))
      (node (ref "R6") (pin "1") (pinfunction "1_1") (pintype "passive"))
    )
    (net (code "52") (name "Net-(Q2A-S)") (class "Default")
      (node (ref "Q2") (pin "1") (pinfunction "S_1") (pintype "passive"))
      (node (ref "R7") (pin "2") (pinfunction "2_2") (pintype "passive"))
      (node (ref "U2") (pin "28") (pinfunction "DTR_28") (pintype "output"))
    )
    (net (code "53") (name "Net-(Q2B-D)") (class "Default")
      (node (ref "Q2") (pin "3") (pinfunction "D_3") (pintype "passive"))
      (node (ref "R6") (pin "2") (pinfunction "2_2") (pintype "passive"))
      (node (ref "U2") (pin "24") (pinfunction "RTS_24") (pintype "output"))
    )
    (net (code "54") (name "Net-(Q2B-G)") (class "Default")
      (node (ref "Q2") (pin "5") (pinfunction "G_5") (pintype "passive"))
      (node (ref "R7") (pin "1") (pinfunction "1_1") (pintype "passive"))
    )
    (net (code "55") (name "Net-(U2-RSTb)") (class "Default")
      (node (ref "R3") (pin "1") (pinfunction "1_1") (pintype "passive"))
      (node (ref "U2") (pin "9") (pinfunction "RSTb_9") (pintype "input"))
    )
    (net (code "56") (name "Net-(U2-VBUS)") (class "Default")
      (node (ref "R4") (pin "1") (pinfunction "1_1") (pintype "passive"))
      (node (ref "R5") (pin "2") (pinfunction "2_2") (pintype "passive"))
      (node (ref "U2") (pin "8") (pinfunction "VBUS_8") (pintype "power_in"))
    )
    (net (code "57") (name "Net-(U5-1_DRAIN)") (class "Default")
      (node (ref "H4") (pin "1") (pinfunction "1_1") (pintype "passive"))
      (node (ref "U5") (pin "3") (pinfunction "1_DRAIN_3") (pintype "passive"))
    )
    (net (code "58") (name "Net-(U5-2_DRAIN)") (class "Default")
      (node (ref "R10") (pin "1") (pinfunction "1_1") (pintype "passive"))
      (node (ref "U5") (pin "4") (pinfunction "2_DRAIN_4") (pintype "passive"))
    )
    (net (code "59") (name "Net-(U5-A)") (class "Default")
      (node (ref "R9") (pin "2") (pinfunction "2_2") (pintype "passive"))
      (node (ref "U5") (pin "1") (pinfunction "A_1") (pintype "passive"))
    )
    (net (code "60") (name "VBUS") (class "Default")
      (node (ref "D3") (pin "2") (pinfunction "A_2") (pintype "passive"))
      (node (ref "H3") (pin "13") (pinfunction "13_13") (pintype "passive"))
      (node (ref "Q1") (pin "3") (pinfunction "D_3") (pintype "passive"))
    )
    (net (code "61") (name "VUSB") (class "Default")
      (node (ref "C1") (pin "1") (pinfunction "1_1") (pintype "passive"))
      (node (ref "C3") (pin "1") (pinfunction "1_1") (pintype "passive"))
      (node (ref "D1") (pin "2") (pinfunction "A_2") (pintype "passive"))
      (node (ref "D2") (pin "2") (pinfunction "A_2") (pintype "passive"))
      (node (ref "H1") (pin "A4_B9") (pinfunction "VBUS_A4_B9") (pintype "power_in"))
      (node (ref "H1") (pin "B4_A9") (pinfunction "VBUS_B4_A9") (pintype "power_in"))
      (node (ref "Q1") (pin "1") (pinfunction "G_1") (pintype "passive"))
      (node (ref "R3") (pin "2") (pinfunction "2_2") (pintype "passive"))
      (node (ref "R4") (pin "2") (pinfunction "2_2") (pintype "passive"))
      (node (ref "U1") (pin "4") (pinfunction "L3_4") (pintype "passive"))
      (node (ref "U2") (pin "6") (pinfunction "VDD_6") (pintype "power_in"))
      (node (ref "U2") (pin "7") (pinfunction "VREGIN_7") (pintype "power_in"))
    )
    (net (code "62") (name "unconnected-(H1-SBU1-PadA8)") (class "Default")
      (node (ref "H1") (pin "A8") (pinfunction "SBU1_A8") (pintype "power_in+no_connect"))
    )
    (net (code "63") (name "unconnected-(H1-SBU2-PadB8)") (class "Default")
      (node (ref "H1") (pin "B8") (pinfunction "SBU2_B8") (pintype "power_in+no_connect"))
    )
    (net (code "64") (name "unconnected-(H2-Pad01)") (class "Default")
      (node (ref "H2") (pin "01") (pinfunction "01_01") (pintype "passive"))
    )
    (net (code "65") (name "unconnected-(H2-Pad02)") (class "Default")
      (node (ref "H2") (pin "02") (pinfunction "02_02") (pintype "passive"))
    )
    (net (code "66") (name "unconnected-(H2-Pad03)") (class "Default")
      (node (ref "H2") (pin "03") (pinfunction "03_03") (pintype "passive"))
    )
    (net (code "67") (name "unconnected-(H2-Pad04)") (class "Default")
      (node (ref "H2") (pin "04") (pinfunction "04_04") (pintype "passive"))
    )
    (net (code "68") (name "unconnected-(H2-Pad05)") (class "Default")
      (node (ref "H2") (pin "05") (pinfunction "05_05") (pintype "passive"))
    )
    (net (code "69") (name "unconnected-(H2-Pad06)") (class "Default")
      (node (ref "H2") (pin "06") (pinfunction "06_06") (pintype "passive"))
    )
    (net (code "70") (name "unconnected-(H2-Pad07)") (class "Default")
      (node (ref "H2") (pin "07") (pinfunction "07_07") (pintype "passive"))
    )
    (net (code "71") (name "unconnected-(H2-Pad08)") (class "Default")
      (node (ref "H2") (pin "08") (pinfunction "08_08") (pintype "passive"))
    )
    (net (code "72") (name "unconnected-(H2-Pad09)") (class "Default")
      (node (ref "H2") (pin "09") (pinfunction "09_09") (pintype "passive"))
    )
    (net (code "73") (name "unconnected-(H2-Pad10)") (class "Default")
      (node (ref "H2") (pin "10") (pinfunction "10_10") (pintype "passive"))
    )
    (net (code "74") (name "unconnected-(H2-Pad11)") (class "Default")
      (node (ref "H2") (pin "11") (pinfunction "11_11") (pintype "passive"))
    )
    (net (code "75") (name "unconnected-(H2-Pad12)") (class "Default")
      (node (ref "H2") (pin "12") (pinfunction "12_12") (pintype "passive"))
    )
    (net (code "76") (name "unconnected-(H2-Pad13)") (class "Default")
      (node (ref "H2") (pin "13") (pinfunction "13_13") (pintype "passive"))
    )
    (net (code "77") (name "unconnected-(H2-Pad14)") (class "Default")
      (node (ref "H2") (pin "14") (pinfunction "14_14") (pintype "passive"))
    )
    (net (code "78") (name "unconnected-(H2-Pad15)") (class "Default")
      (node (ref "H2") (pin "15") (pinfunction "15_15") (pintype "passive"))
    )
    (net (code "79") (name "unconnected-(H2-Pad16)") (class "Default")
      (node (ref "H2") (pin "16") (pinfunction "16_16") (pintype "passive"))
    )
    (net (code "80") (name "unconnected-(H2-Pad17)") (class "Default")
      (node (ref "H2") (pin "17") (pinfunction "17_17") (pintype "passive"))
    )
    (net (code "81") (name "unconnected-(H2-Pad18)") (class "Default")
      (node (ref "H2") (pin "18") (pinfunction "18_18") (pintype "passive"))
    )
    (net (code "82") (name "unconnected-(H2-Pad19)") (class "Default")
      (node (ref "H2") (pin "19") (pinfunction "19_19") (pintype "passive"))
    )
    (net (code "83") (name "unconnected-(H2-Pad20)") (class "Default")
      (node (ref "H2") (pin "20") (pinfunction "20_20") (pintype "passive"))
    )
    (net (code "84") (name "unconnected-(H2-Pad21)") (class "Default")
      (node (ref "H2") (pin "21") (pinfunction "21_21") (pintype "passive"))
    )
    (net (code "85") (name "unconnected-(H2-Pad22)") (class "Default")
      (node (ref "H2") (pin "22") (pinfunction "22_22") (pintype "passive"))
    )
    (net (code "86") (name "unconnected-(H2-Pad23)") (class "Default")
      (node (ref "H2") (pin "23") (pinfunction "23_23") (pintype "passive"))
    )
    (net (code "87") (name "unconnected-(H2-Pad24)") (class "Default")
      (node (ref "H2") (pin "24") (pinfunction "24_24") (pintype "passive"))
    )
    (net (code "88") (name "unconnected-(H2-Pad25)") (class "Default")
      (node (ref "H2") (pin "25") (pinfunction "25_25") (pintype "passive"))
    )
    (net (code "89") (name "unconnected-(H2-Pad26)") (class "Default")
      (node (ref "H2") (pin "26") (pinfunction "26_26") (pintype "passive"))
    )
    (net (code "90") (name "unconnected-(H2-Pad27)") (class "Default")
      (node (ref "H2") (pin "27") (pinfunction "27_27") (pintype "passive"))
    )
    (net (code "91") (name "unconnected-(H2-Pad28)") (class "Default")
      (node (ref "H2") (pin "28") (pinfunction "28_28") (pintype "passive"))
    )
    (net (code "92") (name "unconnected-(H2-Pad29)") (class "Default")
      (node (ref "H2") (pin "29") (pinfunction "29_29") (pintype "passive"))
    )
    (net (code "93") (name "unconnected-(H2-Pad30)") (class "Default")
      (node (ref "H2") (pin "30") (pinfunction "30_30") (pintype "passive"))
    )
    (net (code "94") (name "unconnected-(H2-Pad31)") (class "Default")
      (node (ref "H2") (pin "31") (pinfunction "31_31") (pintype "passive"))
    )
    (net (code "95") (name "unconnected-(H2-Pad32)") (class "Default")
      (node (ref "H2") (pin "32") (pinfunction "32_32") (pintype "passive"))
    )
    (net (code "96") (name "unconnected-(H2-Pad33)") (class "Default")
      (node (ref "H2") (pin "33") (pinfunction "33_33") (pintype "passive"))
    )
    (net (code "97") (name "unconnected-(H2-Pad34)") (class "Default")
      (node (ref "H2") (pin "34") (pinfunction "34_34") (pintype "passive"))
    )
    (net (code "98") (name "unconnected-(H2-Pad35)") (class "Default")
      (node (ref "H2") (pin "35") (pinfunction "35_35") (pintype "passive"))
    )
    (net (code "99") (name "unconnected-(H2-Pad36)") (class "Default")
      (node (ref "H2") (pin "36") (pinfunction "36_36") (pintype "passive"))
    )
    (net (code "100") (name "unconnected-(H2-Pad37)") (class "Default")
      (node (ref "H2") (pin "37") (pinfunction "37_37") (pintype "passive"))
    )
    (net (code "101") (name "unconnected-(H2-Pad38)") (class "Default")
      (node (ref "H2") (pin "38") (pinfunction "38_38") (pintype "passive"))
    )
    (net (code "102") (name "unconnected-(H2-Pad39)") (class "Default")
      (node (ref "H2") (pin "39") (pinfunction "39_39") (pintype "passive"))
    )
    (net (code "103") (name "unconnected-(H2-Pad40)") (class "Default")
      (node (ref "H2") (pin "40") (pinfunction "40_40") (pintype "passive"))
    )
    (net (code "104") (name "unconnected-(H2-Pad42)") (class "Default")
      (node (ref "H2") (pin "42") (pinfunction "42_42") (pintype "passive"))
    )
    (net (code "105") (name "unconnected-(H2-Pad44)") (class "Default")
      (node (ref "H2") (pin "44") (pinfunction "44_44") (pintype "passive"))
    )
    (net (code "106") (name "unconnected-(H2-Pad45)") (class "Default")
      (node (ref "H2") (pin "45") (pinfunction "45_45") (pintype "passive"))
    )
    (net (code "107") (name "unconnected-(H2-Pad46)") (class "Default")
      (node (ref "H2") (pin "46") (pinfunction "46_46") (pintype "passive"))
    )
    (net (code "108") (name "unconnected-(H2-Pad47)") (class "Default")
      (node (ref "H2") (pin "47") (pinfunction "47_47") (pintype "passive"))
    )
    (net (code "109") (name "unconnected-(H2-Pad48)") (class "Default")
      (node (ref "H2") (pin "48") (pinfunction "48_48") (pintype "passive"))
    )
    (net (code "110") (name "unconnected-(H2-Pad49)") (class "Default")
      (node (ref "H2") (pin "49") (pinfunction "49_49") (pintype "passive"))
    )
    (net (code "111") (name "unconnected-(H2-Pad50)") (class "Default")
      (node (ref "H2") (pin "50") (pinfunction "50_50") (pintype "passive"))
    )
    (net (code "112") (name "unconnected-(H2-Pad51)") (class "Default")
      (node (ref "H2") (pin "51") (pinfunction "51_51") (pintype "passive"))
    )
    (net (code "113") (name "unconnected-(H2-Pad52)") (class "Default")
      (node (ref "H2") (pin "52") (pinfunction "52_52") (pintype "passive"))
    )
    (net (code "114") (name "unconnected-(H3-Pad01)") (class "Default")
      (node (ref "H3") (pin "01") (pinfunction "01_01") (pintype "passive"))
    )
    (net (code "115") (name "unconnected-(H3-Pad02)") (class "Default")
      (node (ref "H3") (pin "02") (pinfunction "02_02") (pintype "passive"))
    )
    (net (code "116") (name "unconnected-(H3-Pad03)") (class "Default")
      (node (ref "H3") (pin "03") (pinfunction "03_03") (pintype "passive"))
    )
    (net (code "117") (name "unconnected-(H3-Pad04)") (class "Default")
      (node (ref "H3") (pin "04") (pinfunction "04_04") (pintype "passive"))
    )
    (net (code "118") (name "unconnected-(H3-Pad05)") (class "Default")
      (node (ref "H3") (pin "05") (pinfunction "05_05") (pintype "passive"))
    )
    (net (code "119") (name "unconnected-(H3-Pad06)") (class "Default")
      (node (ref "H3") (pin "06") (pinfunction "06_06") (pintype "passive"))
    )
    (net (code "120") (name "unconnected-(H3-Pad07)") (class "Default")
      (node (ref "H3") (pin "07") (pinfunction "07_07") (pintype "passive"))
    )
    (net (code "121") (name "unconnected-(H3-Pad08)") (class "Default")
      (node (ref "H3") (pin "08") (pinfunction "08_08") (pintype "passive"))
    )
    (net (code "122") (name "unconnected-(H3-Pad10)") (class "Default")
      (node (ref "H3") (pin "10") (pinfunction "10_10") (pintype "passive"))
    )
    (net (code "123") (name "unconnected-(H3-Pad11)") (class "Default")
      (node (ref "H3") (pin "11") (pinfunction "11_11") (pintype "passive"))
    )
    (net (code "124") (name "unconnected-(H3-Pad12)") (class "Default")
      (node (ref "H3") (pin "12") (pinfunction "12_12") (pintype "passive"))
    )
    (net (code "125") (name "unconnected-(H3-Pad15)") (class "Default")
      (node (ref "H3") (pin "15") (pinfunction "15_15") (pintype "passive"))
    )
    (net (code "126") (name "unconnected-(H3-Pad16)") (class "Default")
      (node (ref "H3") (pin "16") (pinfunction "16_16") (pintype "passive"))
    )
    (net (code "127") (name "unconnected-(H3-Pad18)") (class "Default")
      (node (ref "H3") (pin "18") (pinfunction "18_18") (pintype "passive"))
    )
    (net (code "128") (name "unconnected-(H3-Pad19)") (class "Default")
      (node (ref "H3") (pin "19") (pinfunction "19_19") (pintype "passive"))
    )
    (net (code "129") (name "unconnected-(H3-Pad20)") (class "Default")
      (node (ref "H3") (pin "20") (pinfunction "20_20") (pintype "passive"))
    )
    (net (code "130") (name "unconnected-(H3-Pad23)") (class "Default")
      (node (ref "H3") (pin "23") (pinfunction "23_23") (pintype "passive"))
    )
    (net (code "131") (name "unconnected-(H3-Pad24)") (class "Default")
      (node (ref "H3") (pin "24") (pinfunction "24_24") (pintype "passive"))
    )
    (net (code "132") (name "unconnected-(H3-Pad26)") (class "Default")
      (node (ref "H3") (pin "26") (pinfunction "26_26") (pintype "passive"))
    )
    (net (code "133") (name "unconnected-(H3-Pad27)") (class "Default")
      (node (ref "H3") (pin "27") (pinfunction "27_27") (pintype "passive"))
    )
    (net (code "134") (name "unconnected-(H3-Pad28)") (class "Default")
      (node (ref "H3") (pin "28") (pinfunction "28_28") (pintype "passive"))
    )
    (net (code "135") (name "unconnected-(H3-Pad31)") (class "Default")
      (node (ref "H3") (pin "31") (pinfunction "31_31") (pintype "passive"))
    )
    (net (code "136") (name "unconnected-(H3-Pad33)") (class "Default")
      (node (ref "H3") (pin "33") (pinfunction "33_33") (pintype "passive"))
    )
    (net (code "137") (name "unconnected-(H3-Pad34)") (class "Default")
      (node (ref "H3") (pin "34") (pinfunction "34_34") (pintype "passive"))
    )
    (net (code "138") (name "unconnected-(H3-Pad35)") (class "Default")
      (node (ref "H3") (pin "35") (pinfunction "35_35") (pintype "passive"))
    )
    (net (code "139") (name "unconnected-(H3-Pad36)") (class "Default")
      (node (ref "H3") (pin "36") (pinfunction "36_36") (pintype "passive"))
    )
    (net (code "140") (name "unconnected-(H3-Pad37)") (class "Default")
      (node (ref "H3") (pin "37") (pinfunction "37_37") (pintype "passive"))
    )
    (net (code "141") (name "unconnected-(H3-Pad38)") (class "Default")
      (node (ref "H3") (pin "38") (pinfunction "38_38") (pintype "passive"))
    )
    (net (code "142") (name "unconnected-(H3-Pad39)") (class "Default")
      (node (ref "H3") (pin "39") (pinfunction "39_39") (pintype "passive"))
    )
    (net (code "143") (name "unconnected-(H3-Pad40)") (class "Default")
      (node (ref "H3") (pin "40") (pinfunction "40_40") (pintype "passive"))
    )
    (net (code "144") (name "unconnected-(H3-Pad41)") (class "Default")
      (node (ref "H3") (pin "41") (pinfunction "41_41") (pintype "passive"))
    )
    (net (code "145") (name "unconnected-(H3-Pad42)") (class "Default")
      (node (ref "H3") (pin "42") (pinfunction "42_42") (pintype "passive"))
    )
    (net (code "146") (name "unconnected-(H3-Pad43)") (class "Default")
      (node (ref "H3") (pin "43") (pinfunction "43_43") (pintype "passive"))
    )
    (net (code "147") (name "unconnected-(H3-Pad44)") (class "Default")
      (node (ref "H3") (pin "44") (pinfunction "44_44") (pintype "passive"))
    )
    (net (code "148") (name "unconnected-(H3-Pad45)") (class "Default")
      (node (ref "H3") (pin "45") (pinfunction "45_45") (pintype "passive"))
    )
    (net (code "149") (name "unconnected-(H3-Pad46)") (class "Default")
      (node (ref "H3") (pin "46") (pinfunction "46_46") (pintype "passive"))
    )
    (net (code "150") (name "unconnected-(H3-Pad49)") (class "Default")
      (node (ref "H3") (pin "49") (pinfunction "49_49") (pintype "passive"))
    )
    (net (code "151") (name "unconnected-(H3-Pad50)") (class "Default")
      (node (ref "H3") (pin "50") (pinfunction "50_50") (pintype "passive"))
    )
    (net (code "152") (name "unconnected-(H3-Pad51)") (class "Default")
      (node (ref "H3") (pin "51") (pinfunction "51_51") (pintype "passive"))
    )
    (net (code "153") (name "unconnected-(H3-Pad52)") (class "Default")
      (node (ref "H3") (pin "52") (pinfunction "52_52") (pintype "passive"))
    )
    (net (code "154") (name "unconnected-(U1-L4-Pad5)") (class "Default")
      (node (ref "U1") (pin "5") (pinfunction "L4_5") (pintype "passive+no_connect"))
    )
    (net (code "155") (name "unconnected-(U1-L5-Pad6)") (class "Default")
      (node (ref "U1") (pin "6") (pinfunction "L5_6") (pintype "passive"))
    )
    (net (code "156") (name "unconnected-(U2-CHR0-Pad15)") (class "Default")
      (node (ref "U2") (pin "15") (pinfunction "CHR0_15") (pintype "output+no_connect"))
    )
    (net (code "157") (name "unconnected-(U2-CHR1-Pad14)") (class "Default")
      (node (ref "U2") (pin "14") (pinfunction "CHR1_14") (pintype "output+no_connect"))
    )
    (net (code "158") (name "unconnected-(U2-CHREN-Pad13)") (class "Default")
      (node (ref "U2") (pin "13") (pinfunction "CHREN_13") (pintype "output+no_connect"))
    )
    (net (code "159") (name "unconnected-(U2-CTS-Pad23)") (class "Default")
      (node (ref "U2") (pin "23") (pinfunction "CTS_23") (pintype "input+no_connect"))
    )
    (net (code "160") (name "unconnected-(U2-DCD-Pad1)") (class "Default")
      (node (ref "U2") (pin "1") (pinfunction "DCD_1") (pintype "input+no_connect"))
    )
    (net (code "161") (name "unconnected-(U2-DSR-Pad27)") (class "Default")
      (node (ref "U2") (pin "27") (pinfunction "DSR_27") (pintype "input+no_connect"))
    )
    (net (code "162") (name "unconnected-(U2-GPIO.0_{slash}_TXT-Pad19)") (class "Default")
      (node (ref "U2") (pin "19") (pinfunction "GPIO.0_/_TXT_19") (pintype "bidirectional+no_connect"))
    )
    (net (code "163") (name "unconnected-(U2-GPIO.1_{slash}_RXT-Pad18)") (class "Default")
      (node (ref "U2") (pin "18") (pinfunction "GPIO.1_/_RXT_18") (pintype "bidirectional+no_connect"))
    )
    (net (code "164") (name "unconnected-(U2-GPIO.2_{slash}_RS485-Pad17)") (class "Default")
      (node (ref "U2") (pin "17") (pinfunction "GPIO.2_/_RS485_17") (pintype "bidirectional+no_connect"))
    )
    (net (code "165") (name "unconnected-(U2-GPIO.3_{slash}_WAKEUP-Pad16)") (class "Default")
      (node (ref "U2") (pin "16") (pinfunction "GPIO.3_/_WAKEUP_16") (pintype "bidirectional+no_connect"))
    )
    (net (code "166") (name "unconnected-(U2-GPIO.4-Pad22)") (class "Default")
      (node (ref "U2") (pin "22") (pinfunction "GPIO.4_22") (pintype "bidirectional+no_connect"))
    )
    (net (code "167") (name "unconnected-(U2-GPIO.5-Pad21)") (class "Default")
      (node (ref "U2") (pin "21") (pinfunction "GPIO.5_21") (pintype "bidirectional+no_connect"))
    )
    (net (code "168") (name "unconnected-(U2-GPIO.6-Pad20)") (class "Default")
      (node (ref "U2") (pin "20") (pinfunction "GPIO.6_20") (pintype "bidirectional+no_connect"))
    )
    (net (code "169") (name "unconnected-(U2-NC-Pad10)") (class "Default")
      (node (ref "U2") (pin "10") (pinfunction "NC_10") (pintype "passive+no_connect"))
    )
    (net (code "170") (name "unconnected-(U2-RI_{slash}_CLK-Pad2)") (class "Default")
      (node (ref "U2") (pin "2") (pinfunction "RI_/_CLK_2") (pintype "input+no_connect"))
    )
    (net (code "171") (name "unconnected-(U2-SUSPEND-Pad12)") (class "Default")
      (node (ref "U2") (pin "12") (pinfunction "SUSPEND_12") (pintype "output+no_connect"))
    )
    (net (code "172") (name "unconnected-(U2-SUSPENDb-Pad11)") (class "Default")
      (node (ref "U2") (pin "11") (pinfunction "SUSPENDb_11") (pintype "output+no_connect"))
    )
    (net (code "173") (name "unconnected-(U3-NC-Pad4)") (class "Default")
      (node (ref "U3") (pin "4") (pinfunction "NC_4") (pintype "passive+no_connect"))
    )
    (net (code "174") (name "unconnected-(U4-CAP1_NC-Pad48)") (class "Default")
      (node (ref "U4") (pin "48") (pinfunction "CAP1_NC_48") (pintype "passive+no_connect"))
    )
    (net (code "175") (name "unconnected-(U4-CAP2_NC-Pad47)") (class "Default")
      (node (ref "U4") (pin "47") (pinfunction "CAP2_NC_47") (pintype "passive+no_connect"))
    )
    (net (code "176") (name "unconnected-(U4-CLK-Pad31)") (class "Default")
      (node (ref "U4") (pin "31") (pinfunction "CLK_31") (pintype "bidirectional+no_connect"))
    )
    (net (code "177") (name "unconnected-(U4-CMD-Pad30)") (class "Default")
      (node (ref "U4") (pin "30") (pinfunction "CMD_30") (pintype "bidirectional+no_connect"))
    )
    (net (code "178") (name "unconnected-(U4-IO2-Pad22)") (class "Default")
      (node (ref "U4") (pin "22") (pinfunction "IO2_22") (pintype "bidirectional+no_connect"))
    )
    (net (code "179") (name "unconnected-(U4-IO15-Pad21)") (class "Default")
      (node (ref "U4") (pin "21") (pinfunction "IO15_21") (pintype "bidirectional+no_connect"))
    )
    (net (code "180") (name "unconnected-(U4-IO16-Pad25)") (class "Default")
      (node (ref "U4") (pin "25") (pinfunction "IO16_25") (pintype "bidirectional+no_connect"))
    )
    (net (code "181") (name "unconnected-(U4-IO17-Pad27)") (class "Default")
      (node (ref "U4") (pin "27") (pinfunction "IO17_27") (pintype "bidirectional+no_connect"))
    )
    (net (code "182") (name "unconnected-(U4-IO18-Pad35)") (class "Default")
      (node (ref "U4") (pin "35") (pinfunction "IO18_35") (pintype "bidirectional+no_connect"))
    )
    (net (code "183") (name "unconnected-(U4-IO23-Pad36)") (class "Default")
      (node (ref "U4") (pin "36") (pinfunction "IO23_36") (pintype "bidirectional+no_connect"))
    )
    (net (code "184") (name "unconnected-(U4-LNA_IN-Pad2)") (class "Default")
      (node (ref "U4") (pin "2") (pinfunction "LNA_IN_2") (pintype "bidirectional+no_connect"))
    )
    (net (code "185") (name "unconnected-(U4-SD0-Pad32)") (class "Default")
      (node (ref "U4") (pin "32") (pinfunction "SD0_32") (pintype "bidirectional+no_connect"))
    )
    (net (code "186") (name "unconnected-(U4-SD1-Pad33)") (class "Default")
      (node (ref "U4") (pin "33") (pinfunction "SD1_33") (pintype "bidirectional+no_connect"))
    )
    (net (code "187") (name "unconnected-(U4-SD2-Pad28)") (class "Default")
      (node (ref "U4") (pin "28") (pinfunction "SD2_28") (pintype "bidirectional+no_connect"))
    )
    (net (code "188") (name "unconnected-(U4-SD3-Pad29)") (class "Default")
      (node (ref "U4") (pin "29") (pinfunction "SD3_29") (pintype "bidirectional+no_connect"))
    )
    (net (code "189") (name "unconnected-(U4-VDD_SDIO-Pad26)") (class "Default")
      (node (ref "U4") (pin "26") (pinfunction "VDD_SDIO_26") (pintype "bidirectional+no_connect"))
    )
    (net (code "190") (name "unconnected-(U4-XTAL_N_NC-Pad44)") (class "Default")
      (node (ref "U4") (pin "44") (pinfunction "XTAL_N_NC_44") (pintype "passive+no_connect"))
    )
    (net (code "191") (name "unconnected-(U4-XTAL_P_NC-Pad45)") (class "Default")
      (node (ref "U4") (pin "45") (pinfunction "XTAL_P_NC_45") (pintype "passive+no_connect"))
    )
  )
)
